# design.net
KiCad netlist of a schematic drawn in EAGLE
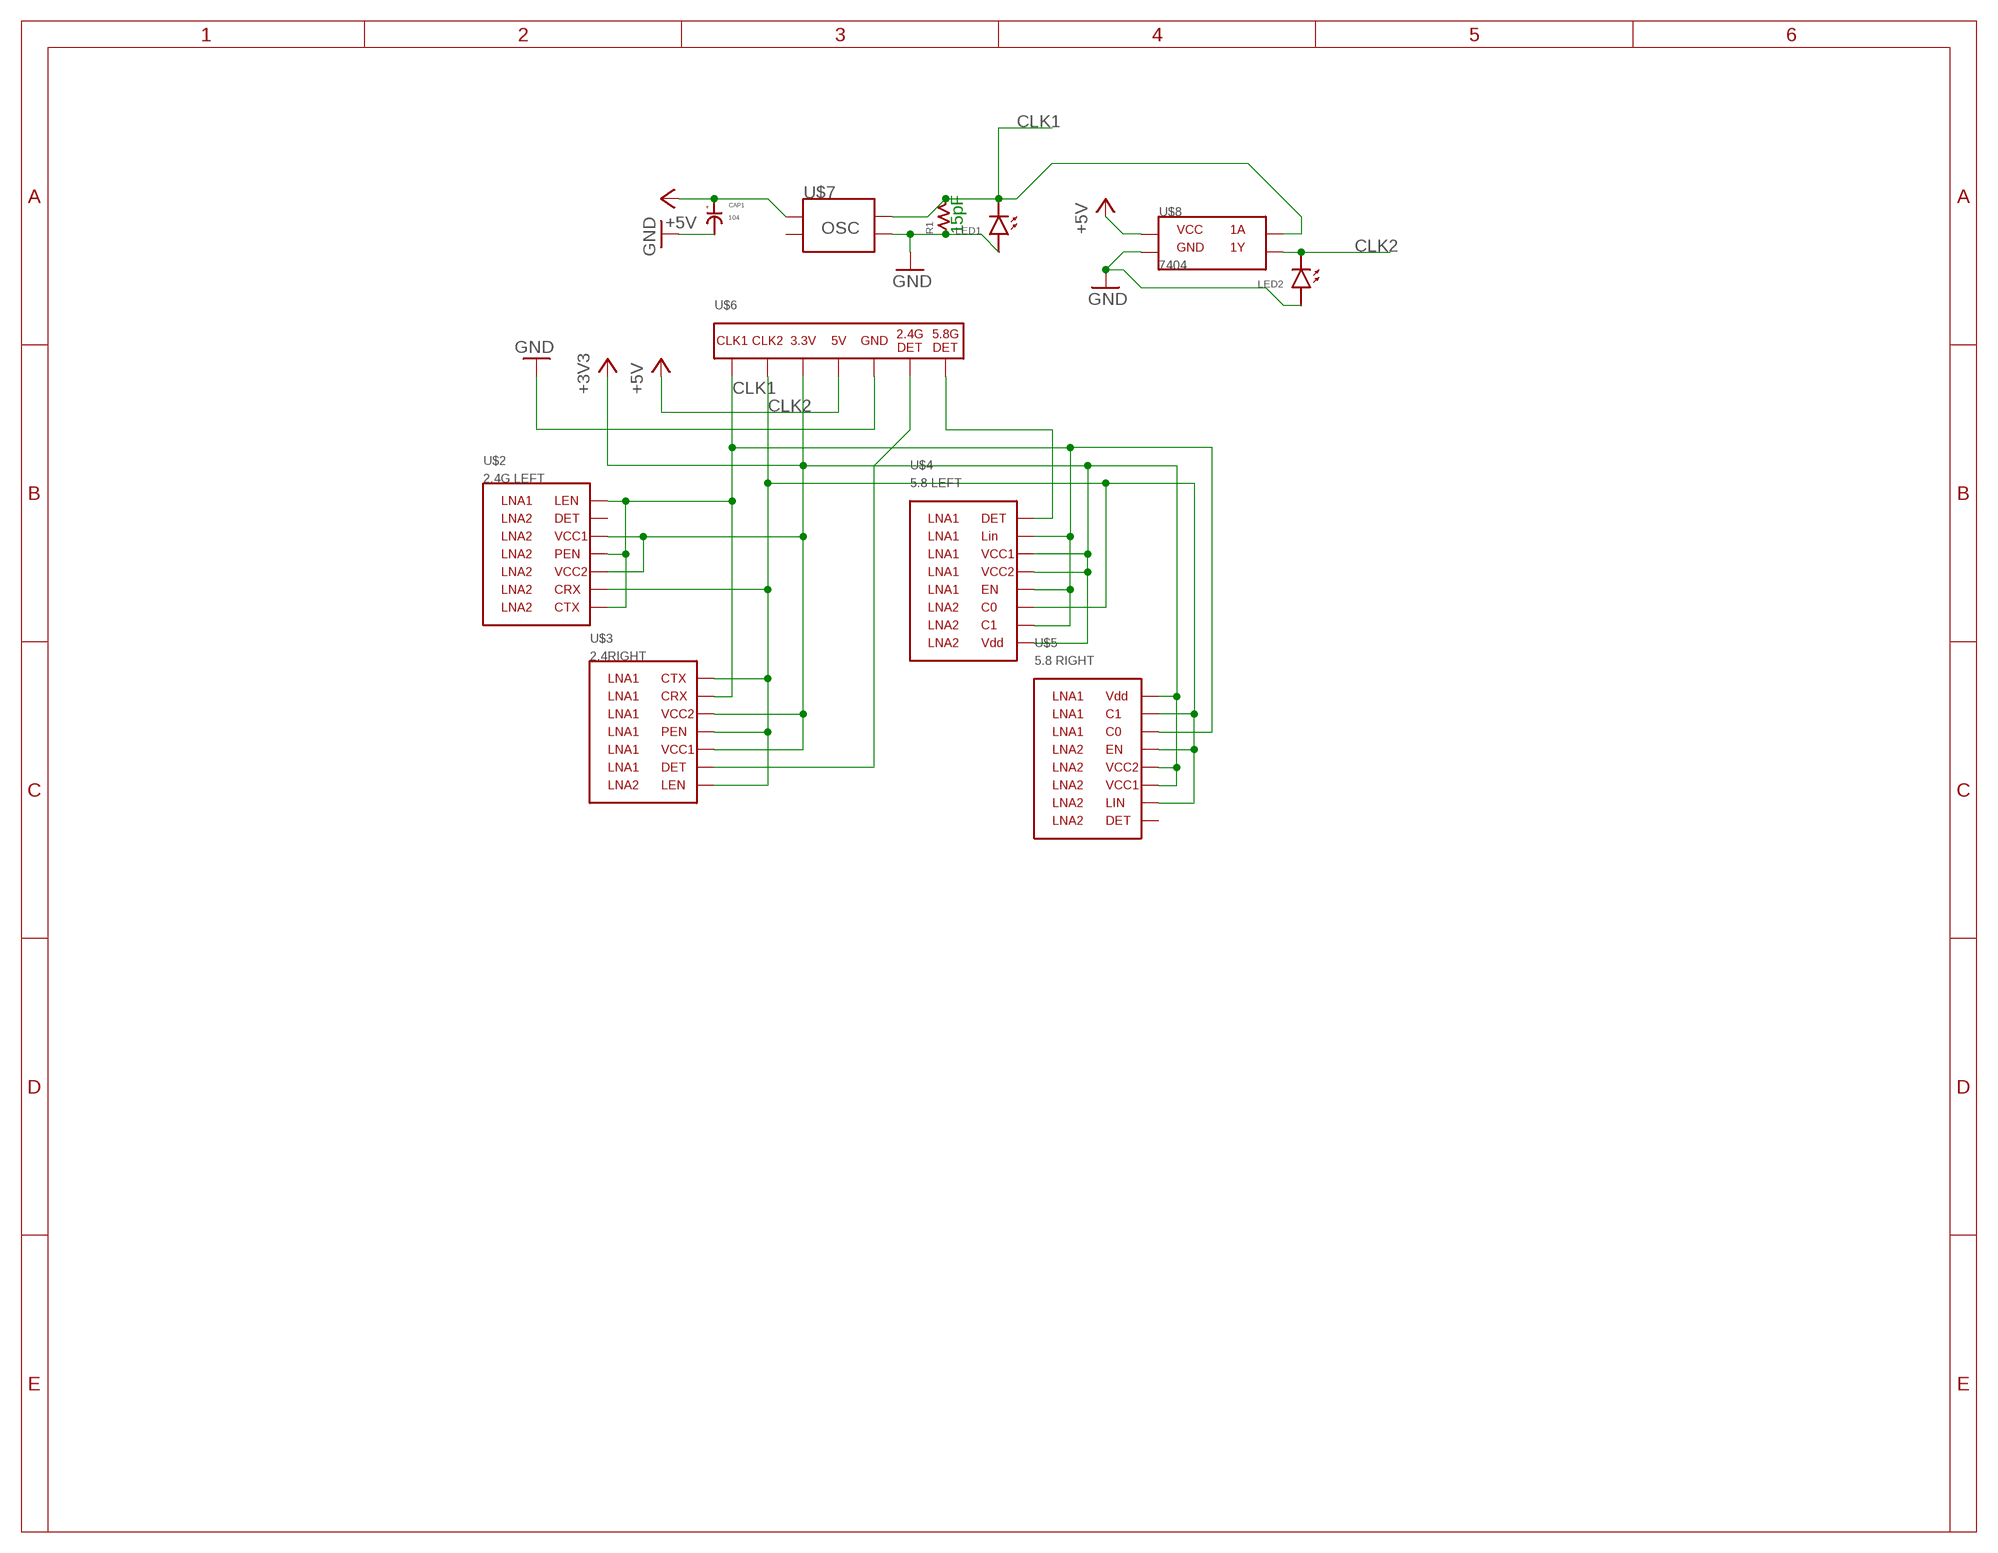
[diagram p0: schematic, sheet 1]

(export (version "E")
  (design (tool "Eeschema 10.0.6"))
  (components
    (comp (ref "CAP1")
      (value "104")
      (footprint "eagle-import:CAP-100MIL")
      (libsource (lib "eagle-import") (part "CAP-100MIL"))
    )
    (comp (ref "LED1")
      (value "LED-5MM")
      (footprint "eagle-import:2-PIN-200MIL-LED")
      (libsource (lib "eagle-import") (part "LED-5MM"))
    )
    (comp (ref "LED2")
      (value "LED-5MM")
      (footprint "eagle-import:2-PIN-200MIL-LED")
      (libsource (lib "eagle-import") (part "LED-5MM"))
    )
    (comp (ref "R1")
      (value "RESISTOR-200MIL")
      (footprint "eagle-import:RESISTOR-200MIL")
      (libsource (lib "eagle-import") (part "RESISTOR-200MIL"))
    )
    (comp (ref "U$2")
      (value "PROJECT-2.4G-LEFTSIDE")
      (footprint "eagle-import:PROJECT-2.4G-LEFTSIDE")
      (libsource (lib "eagle-import") (part "PROJECT-2.4G-LEFTSIDE"))
    )
    (comp (ref "U$3")
      (value "PROJECT-2.4G-RIGHTSIDE")
      (footprint "eagle-import:PROJECT-2.4G-RIGHTSIDE")
      (libsource (lib "eagle-import") (part "PROJECT-2.4G-RIGHTSIDE"))
    )
    (comp (ref "U$4")
      (value "PROJECT-5G-LEFTSIDE")
      (footprint "eagle-import:PROJECT-5G-LEFTSIDE")
      (libsource (lib "eagle-import") (part "PROJECT-5G-LEFTSIDE"))
    )
    (comp (ref "U$5")
      (value "PROJECT-5G-RIGHTSIDE")
      (footprint "eagle-import:PROJECT-5G-RIGHTSIDE")
      (libsource (lib "eagle-import") (part "PROJECT-5G-RIGHTSIDE"))
    )
    (comp (ref "U$6")
      (value "PROJECT-IO")
      (footprint "eagle-import:PROJECT-IO")
      (libsource (lib "eagle-import") (part "PROJECT-IO"))
    )
    (comp (ref "U$7")
      (value "PROJECT-CRYSTAL")
      (footprint "eagle-import:PROJECT-CRYSTAL")
      (libsource (lib "eagle-import") (part "PROJECT-CRYSTAL"))
    )
    (comp (ref "U$8")
      (value "PROJECT-7404")
      (footprint "eagle-import:PROJECT-7404")
      (libsource (lib "eagle-import") (part "PROJECT-7404"))
    )
  )
  (nets
    (net (code "1") (name "+3V3") (class "Default")
      (node (ref "U$2") (pin "VCC1") (pinfunction "VCC1_VCC1") (pintype "bidirectional"))
      (node (ref "U$2") (pin "VCC2") (pinfunction "VCC2_VCC2") (pintype "bidirectional"))
      (node (ref "U$3") (pin "VCC1") (pinfunction "VCC1_VCC1") (pintype "bidirectional"))
      (node (ref "U$3") (pin "VCC2") (pinfunction "VCC2_VCC2") (pintype "bidirectional"))
      (node (ref "U$4") (pin "VCC1") (pinfunction "VCC1_VCC1") (pintype "bidirectional"))
      (node (ref "U$4") (pin "VCC2") (pinfunction "VCC2_VCC2") (pintype "bidirectional"))
      (node (ref "U$4") (pin "VDD") (pinfunction "VDD_VDD") (pintype "bidirectional"))
      (node (ref "U$5") (pin "VCC1") (pinfunction "VCC1_VCC1") (pintype "bidirectional"))
      (node (ref "U$5") (pin "VCC2") (pinfunction "VCC2_VCC2") (pintype "bidirectional"))
      (node (ref "U$5") (pin "VDD") (pinfunction "VDD_VDD") (pintype "bidirectional"))
      (node (ref "U$6") (pin "3.3V") (pinfunction "3.3V_3.3V") (pintype "bidirectional"))
    )
    (net (code "2") (name "+5V") (class "Default")
      (node (ref "CAP1") (pin "P$1") (pinfunction "P$1_P$1") (pintype "bidirectional"))
      (node (ref "U$6") (pin "5V") (pinfunction "5V_5V") (pintype "bidirectional"))
      (node (ref "U$7") (pin "P$1") (pinfunction "P$1_P$1") (pintype "bidirectional"))
      (node (ref "U$8") (pin "P$14") (pinfunction "P$14_P$14") (pintype "bidirectional"))
    )
    (net (code "3") (name "/CLK1") (class "Default")
      (node (ref "LED1") (pin "L-") (pinfunction "LED-_L-") (pintype "bidirectional"))
      (node (ref "R1") (pin "P$2") (pinfunction "P$2_P$2") (pintype "bidirectional"))
      (node (ref "U$2") (pin "CTX") (pinfunction "CTX_CTX") (pintype "bidirectional"))
      (node (ref "U$2") (pin "LEN") (pinfunction "LEN_LEN") (pintype "bidirectional"))
      (node (ref "U$2") (pin "PEN") (pinfunction "PEN_PEN") (pintype "bidirectional"))
      (node (ref "U$3") (pin "CRX") (pinfunction "CRX_CRX") (pintype "bidirectional"))
      (node (ref "U$4") (pin "C1") (pinfunction "C1_C1") (pintype "bidirectional"))
      (node (ref "U$4") (pin "EN") (pinfunction "EN_EN") (pintype "bidirectional"))
      (node (ref "U$4") (pin "LIN") (pinfunction "LIN_LIN") (pintype "bidirectional"))
      (node (ref "U$5") (pin "C0") (pinfunction "C0_C0") (pintype "bidirectional"))
      (node (ref "U$6") (pin "CLK1") (pinfunction "CLK1_CLK1") (pintype "bidirectional"))
      (node (ref "U$7") (pin "P$4") (pinfunction "P$4_P$4") (pintype "bidirectional"))
      (node (ref "U$8") (pin "P$1") (pinfunction "P$1_P$1") (pintype "bidirectional"))
    )
    (net (code "4") (name "/CLK2") (class "Default")
      (node (ref "LED2") (pin "L-") (pinfunction "LED-_L-") (pintype "bidirectional"))
      (node (ref "U$2") (pin "CRX") (pinfunction "CRX_CRX") (pintype "bidirectional"))
      (node (ref "U$3") (pin "CTX") (pinfunction "CTX_CTX") (pintype "bidirectional"))
      (node (ref "U$3") (pin "LEN") (pinfunction "LEN_LEN") (pintype "bidirectional"))
      (node (ref "U$3") (pin "PEN") (pinfunction "PEN_PEN") (pintype "bidirectional"))
      (node (ref "U$4") (pin "C0") (pinfunction "C0_C0") (pintype "bidirectional"))
      (node (ref "U$5") (pin "C1") (pinfunction "C1_C1") (pintype "bidirectional"))
      (node (ref "U$5") (pin "EN") (pinfunction "EN_EN") (pintype "bidirectional"))
      (node (ref "U$5") (pin "LIN") (pinfunction "LIN_LIN") (pintype "bidirectional"))
      (node (ref "U$6") (pin "CLK2") (pinfunction "CLK2_CLK2") (pintype "bidirectional"))
      (node (ref "U$8") (pin "P$2") (pinfunction "P$2_P$2") (pintype "bidirectional"))
    )
    (net (code "5") (name "GND") (class "Default")
      (node (ref "CAP1") (pin "P$2") (pinfunction "P$2_P$2") (pintype "bidirectional"))
      (node (ref "LED1") (pin "L+") (pinfunction "LED+_L+") (pintype "bidirectional"))
      (node (ref "LED2") (pin "L+") (pinfunction "LED+_L+") (pintype "bidirectional"))
      (node (ref "R1") (pin "P$1") (pinfunction "P$1_P$1") (pintype "bidirectional"))
      (node (ref "U$6") (pin "GND") (pinfunction "GND_GND") (pintype "bidirectional"))
      (node (ref "U$7") (pin "P$3") (pinfunction "P$3_P$3") (pintype "bidirectional"))
      (node (ref "U$8") (pin "P$7") (pinfunction "P$7_P$7") (pintype "bidirectional"))
    )
    (net (code "6") (name "Net-(U$3-PadDET)") (class "Default")
      (node (ref "U$3") (pin "DET") (pinfunction "DET_DET") (pintype "bidirectional"))
      (node (ref "U$6") (pin "2.4DET") (pinfunction "2.4DET_2.4DET") (pintype "bidirectional"))
    )
    (net (code "7") (name "Net-(U$4-PadDET)") (class "Default")
      (node (ref "U$4") (pin "DET") (pinfunction "DET_DET") (pintype "bidirectional"))
      (node (ref "U$6") (pin "5.8DET") (pinfunction "5.8DET_5.8DET") (pintype "bidirectional"))
    )
    (net (code "8") (name "unconnected-(U$2-PadDET)") (class "Default")
      (node (ref "U$2") (pin "DET") (pinfunction "DET_DET") (pintype "bidirectional"))
    )
    (net (code "9") (name "unconnected-(U$5-PadDET)") (class "Default")
      (node (ref "U$5") (pin "DET") (pinfunction "DET_DET") (pintype "bidirectional"))
    )
    (net (code "10") (name "unconnected-(U$7-PadP$2)") (class "Default")
      (node (ref "U$7") (pin "P$2") (pinfunction "P$2_P$2") (pintype "bidirectional"))
    )
  )
)
